# ES.net
KiCad netlist of a schematic drawn in Altium Designer
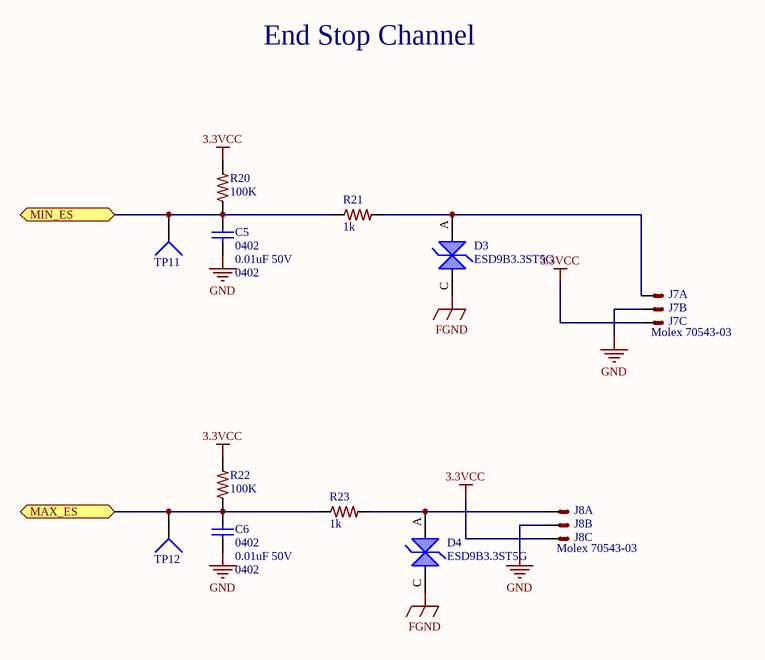
[diagram p0: ES.SchDoc]

(export (version "E")
  (design (tool "Eeschema 10.0.6"))
  (components
    (comp (ref "C5")
      (value "0402")
      (footprint "C0402")
      (description "CAP CER 10nF 50V X7R 0402")
      (fields
        (field (name "ALTIUM_VALUE") "0.01uF 50V")
        (field (name "MFR PART #") "GRM155R71H103JA88D")
        (field (name "MFR") "Murata")
        (field (name "PACKAGEREFERENCE") "0402")
        (field (name "PUBLISHER") "Ultimachine")
      )
      (libsource (lib "Tigershark3D") (part "GRM155R71H103JA88D"))
    )
    (comp (ref "C6")
      (value "0402")
      (footprint "C0402")
      (description "CAP CER 10nF 50V X7R 0402")
      (fields
        (field (name "ALTIUM_VALUE") "0.01uF 50V")
        (field (name "MFR PART #") "GRM155R71H103JA88D")
        (field (name "MFR") "Murata")
        (field (name "PACKAGEREFERENCE") "0402")
        (field (name "PUBLISHER") "Ultimachine")
      )
      (libsource (lib "Tigershark3D") (part "GRM155R71H103JA88D"))
    )
    (comp (ref "D3")
      (value "ESD9B3.3ST5G")
      (footprint "SOD923-100X40-2N")
      (description "11.5 V 15 pF SMT Transient Voltage Suppressor - SOD-923")
      (libsource (lib "3Delight") (part "ESD9B3.3ST5G"))
    )
    (comp (ref "D4")
      (value "ESD9B3.3ST5G")
      (footprint "SOD923-100X40-2N")
      (description "11.5 V 15 pF SMT Transient Voltage Suppressor - SOD-923")
      (libsource (lib "3Delight") (part "ESD9B3.3ST5G"))
    )
    (comp (ref "J7")
      (value "Molex 70543-03")
      (footprint "70543-03")
      (description "Connector 2pos 2.54mm locking")
      (fields (field (name "PUBLISHER") "UltiMachine"))
      (libsource (lib "3Delight") (part "C-GRID-03-70543"))
    )
    (comp (ref "J8")
      (value "Molex 70543-03")
      (footprint "70543-03")
      (description "Connector 2pos 2.54mm locking")
      (fields (field (name "PUBLISHER") "UltiMachine"))
      (libsource (lib "3Delight") (part "C-GRID-03-70543"))
    )
    (comp (ref "R20")
      (value "100K")
      (footprint "R0402")
      (description "RES SMD 100K OHM 1% 1/16W 0402")
      (fields
        (field (name "MANUFACTURER") "Samsung")
        (field (name "MANUFACTURERPARTNUMBER") "RC1005F104CS")
        (field (name "PUBLISHER") "UltiMachine")
      )
      (libsource (lib "Tigershark3D") (part "RC1005F104CS"))
    )
    (comp (ref "R21")
      (value "1k")
      (footprint "R0402")
      (description "RES 0402 1k 63mW 1%")
      (fields (field (name "PUBLISHER") "UltiMachine"))
      (libsource (lib "3Delight") (part "RK73H1ETTP1001F"))
    )
    (comp (ref "R22")
      (value "100K")
      (footprint "R0402")
      (description "RES SMD 100K OHM 1% 1/16W 0402")
      (fields
        (field (name "MANUFACTURER") "Samsung")
        (field (name "MANUFACTURERPARTNUMBER") "RC1005F104CS")
        (field (name "PUBLISHER") "UltiMachine")
      )
      (libsource (lib "Tigershark3D") (part "RC1005F104CS"))
    )
    (comp (ref "R23")
      (value "1k")
      (footprint "R0402")
      (description "RES 0402 1k 63mW 1%")
      (fields (field (name "PUBLISHER") "UltiMachine"))
      (libsource (lib "3Delight") (part "RK73H1ETTP1001F"))
    )
    (comp (ref "TP11")
      (value "TP4")
      (footprint "TP-2")
      (description "Socket")
      (fields (field (name "PUBLISHER") "Altium Limited"))
      (libsource (lib "ZMBo Schematic Library") (part "Socket"))
    )
    (comp (ref "TP12")
      (value "TP4")
      (footprint "TP-2")
      (description "Socket")
      (fields (field (name "PUBLISHER") "Altium Limited"))
      (libsource (lib "ZMBo Schematic Library") (part "Socket"))
    )
  )
  (nets
    (net (code "1") (name "/MAX_ES") (class "Default")
      (node (ref "C6") (pin "1") (pinfunction "1_1") (pintype "passive"))
      (node (ref "R22") (pin "1") (pinfunction "1_1") (pintype "passive"))
      (node (ref "R23") (pin "1") (pinfunction "1_1") (pintype "passive"))
      (node (ref "TP12") (pin "1") (pinfunction "1_1") (pintype "passive"))
    )
    (net (code "2") (name "/MIN_ES") (class "Default")
      (node (ref "C5") (pin "1") (pinfunction "1_1") (pintype "passive"))
      (node (ref "R20") (pin "1") (pinfunction "1_1") (pintype "passive"))
      (node (ref "R21") (pin "1") (pinfunction "1_1") (pintype "passive"))
      (node (ref "TP11") (pin "1") (pinfunction "1_1") (pintype "passive"))
    )
    (net (code "3") (name "3.3VCC") (class "Default")
      (node (ref "J7") (pin "3") (pinfunction "S_3") (pintype "passive"))
      (node (ref "J8") (pin "3") (pinfunction "S_3") (pintype "passive"))
      (node (ref "R20") (pin "2") (pinfunction "2_2") (pintype "passive"))
      (node (ref "R22") (pin "2") (pinfunction "2_2") (pintype "passive"))
    )
    (net (code "4") (name "FGND") (class "Default")
      (node (ref "D3") (pin "C") (pinfunction "C_C") (pintype "power_in"))
      (node (ref "D4") (pin "C") (pinfunction "C_C") (pintype "power_in"))
    )
    (net (code "5") (name "GND") (class "Default")
      (node (ref "C5") (pin "2") (pinfunction "2_2") (pintype "passive"))
      (node (ref "C6") (pin "2") (pinfunction "2_2") (pintype "passive"))
      (node (ref "J7") (pin "2") (pinfunction "S_2") (pintype "passive"))
      (node (ref "J8") (pin "2") (pinfunction "S_2") (pintype "passive"))
    )
    (net (code "6") (name "Net-(J7A-S)") (class "Default")
      (node (ref "D3") (pin "A") (pinfunction "A_A") (pintype "power_in"))
      (node (ref "J7") (pin "1") (pinfunction "S_1") (pintype "passive"))
      (node (ref "R21") (pin "2") (pinfunction "2_2") (pintype "passive"))
    )
    (net (code "7") (name "Net-(J8A-S)") (class "Default")
      (node (ref "D4") (pin "A") (pinfunction "A_A") (pintype "power_in"))
      (node (ref "J8") (pin "1") (pinfunction "S_1") (pintype "passive"))
      (node (ref "R23") (pin "2") (pinfunction "2_2") (pintype "passive"))
    )
  )
)
